# design.net
KiCad netlist of a schematic drawn in Altium Designer
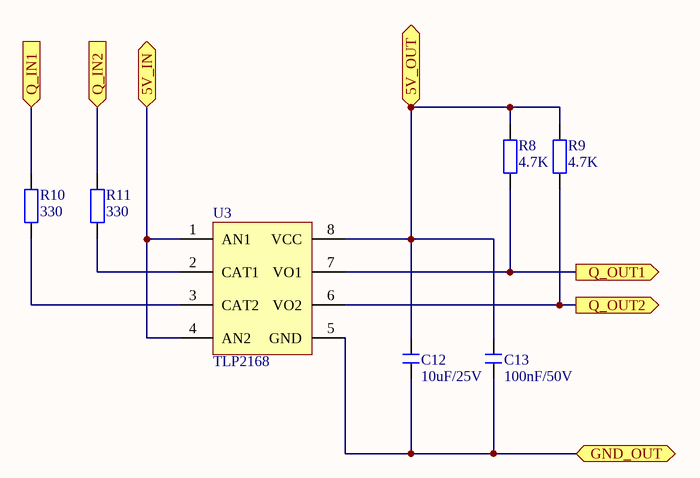
[diagram p0: 第一路数字隔离原理图.SchDoc]

(export (version "E")
  (design (tool "Eeschema 10.0.6"))
  (components
    (comp (ref "C12")
      (value "10uF/25V")
      (footprint "C 0603_M")
      (description "无极性贴片电容")
      (fields (field (name "版权归属") "源创客"))
      (libsource (lib "3.1   - 电阻-电容-电感") (part "C"))
    )
    (comp (ref "C13")
      (value "100nF/50V")
      (footprint "C 0603_M")
      (description "无极性贴片电容")
      (fields (field (name "版权归属") "源创客"))
      (libsource (lib "3.1   - 电阻-电容-电感") (part "C"))
    )
    (comp (ref "R8")
      (value "4.7K")
      (footprint "R 0603_M")
      (description "贴片电阻")
      (fields (field (name "版权归属") "源创客"))
      (libsource (lib "3.1   - 电阻-电容-电感") (part "R"))
    )
    (comp (ref "R9")
      (value "4.7K")
      (footprint "R 0603_M")
      (description "贴片电阻")
      (fields (field (name "版权归属") "源创客"))
      (libsource (lib "3.1   - 电阻-电容-电感") (part "R"))
    )
    (comp (ref "R10")
      (value "330")
      (footprint "R 0603_M")
      (description "贴片电阻")
      (fields (field (name "版权归属") "源创客"))
      (libsource (lib "3.1   - 电阻-电容-电感") (part "R"))
    )
    (comp (ref "R11")
      (value "330")
      (footprint "R 0603_M")
      (description "贴片电阻")
      (fields (field (name "版权归属") "源创客"))
      (libsource (lib "3.1   - 电阻-电容-电感") (part "R"))
    )
    (comp (ref "U3")
      (value "TLP2168")
      (footprint "SOP8_N")
      (description "高速双通道隔离光耦")
      (libsource (lib "1.1   - IC芯片") (part "TLP2168"))
    )
  )
  (nets
    (net (code "1") (name "/5V_IN") (class "Default")
      (node (ref "U3") (pin "1") (pinfunction "AN1_1") (pintype "passive"))
      (node (ref "U3") (pin "4") (pinfunction "AN2_4") (pintype "passive"))
    )
    (net (code "2") (name "/5V_OUT") (class "Default")
      (node (ref "C12") (pin "1") (pinfunction "1_1") (pintype "passive"))
      (node (ref "C13") (pin "2") (pinfunction "2_2") (pintype "passive"))
      (node (ref "R8") (pin "2") (pinfunction "2_2") (pintype "passive"))
      (node (ref "R9") (pin "2") (pinfunction "2_2") (pintype "passive"))
      (node (ref "U3") (pin "8") (pinfunction "VCC_8") (pintype "passive"))
    )
    (net (code "3") (name "/GND_OUT") (class "Default")
      (node (ref "C12") (pin "2") (pinfunction "2_2") (pintype "passive"))
      (node (ref "C13") (pin "1") (pinfunction "1_1") (pintype "passive"))
      (node (ref "U3") (pin "5") (pinfunction "GND_5") (pintype "passive"))
    )
    (net (code "4") (name "/Q_IN1") (class "Default")
      (node (ref "R10") (pin "2") (pinfunction "2_2") (pintype "passive"))
    )
    (net (code "5") (name "/Q_IN2") (class "Default")
      (node (ref "R11") (pin "2") (pinfunction "2_2") (pintype "passive"))
    )
    (net (code "6") (name "/Q_OUT1") (class "Default")
      (node (ref "R8") (pin "1") (pinfunction "1_1") (pintype "passive"))
      (node (ref "U3") (pin "7") (pinfunction "VO1_7") (pintype "passive"))
    )
    (net (code "7") (name "/Q_OUT2") (class "Default")
      (node (ref "R9") (pin "1") (pinfunction "1_1") (pintype "passive"))
      (node (ref "U3") (pin "6") (pinfunction "VO2_6") (pintype "passive"))
    )
    (net (code "8") (name "Net-(U3-CAT1)") (class "Default")
      (node (ref "R11") (pin "1") (pinfunction "1_1") (pintype "passive"))
      (node (ref "U3") (pin "2") (pinfunction "CAT1_2") (pintype "passive"))
    )
    (net (code "9") (name "Net-(U3-CAT2)") (class "Default")
      (node (ref "R10") (pin "1") (pinfunction "1_1") (pintype "passive"))
      (node (ref "U3") (pin "3") (pinfunction "CAT2_3") (pintype "passive"))
    )
  )
)
